# measures_schematic_12-22.net
KiCad netlist of a schematic drawn in EAGLE
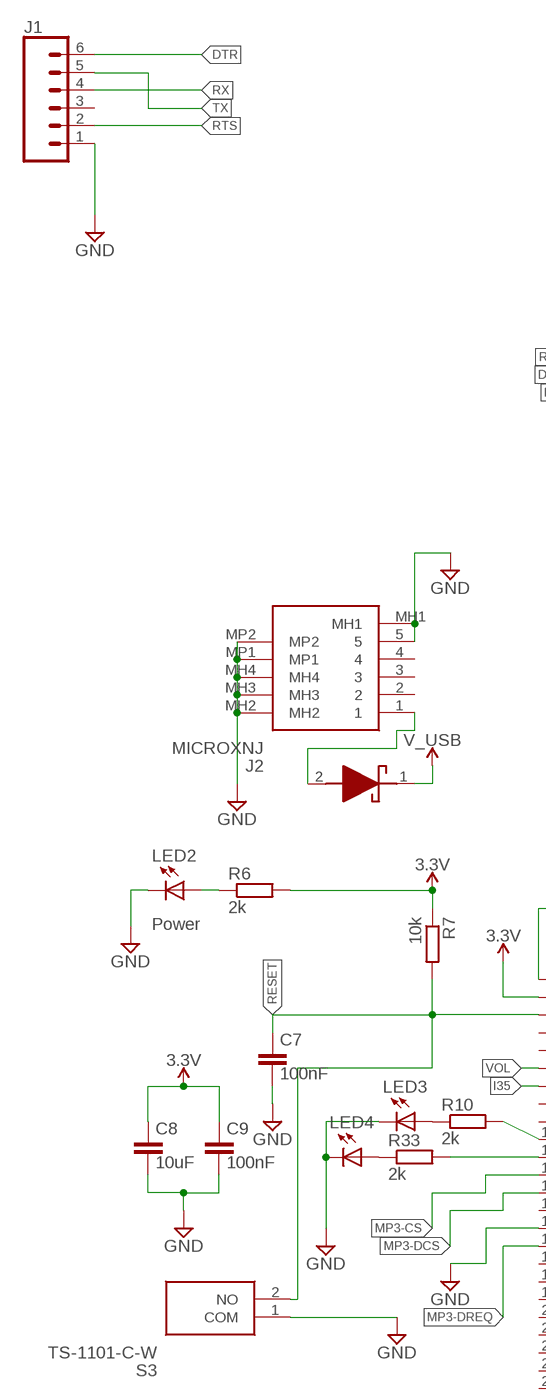
[diagram p0: schematic, sheet 1, part 1 of 2]
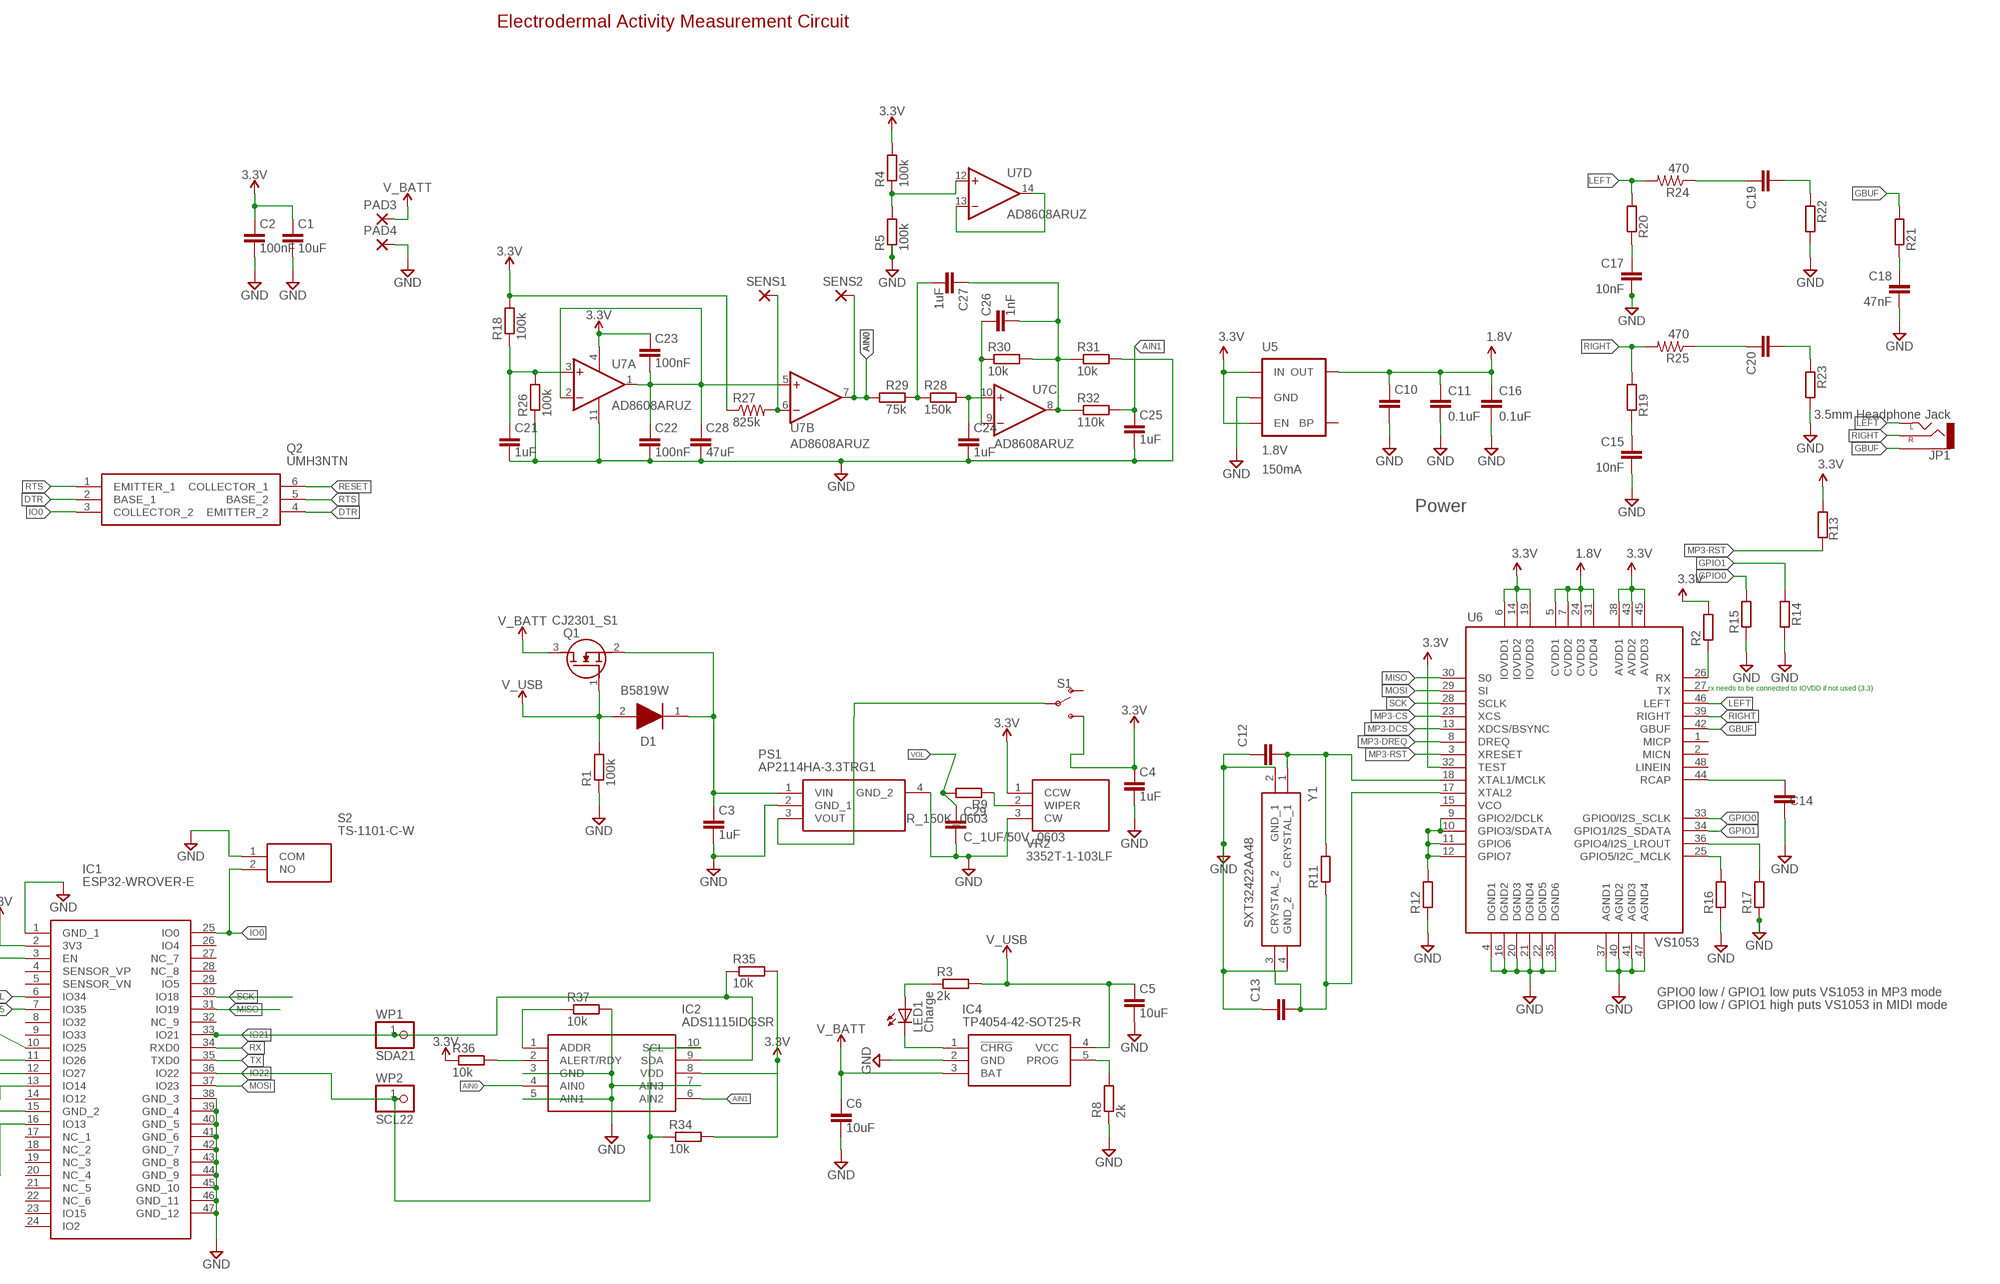
[diagram p1: schematic, sheet 1, part 2 of 2]

(export (version "E")
  (design (tool "Eeschema 10.0.6"))
  (components
    (comp (ref "C1")
      (value "10uF")
      (footprint "eagle-import:C0603")
      (fields (field (name "LCSC_PART") "C96446"))
      (libsource (lib "eagle-import") (part "C__060310UF/25V"))
    )
    (comp (ref "C2")
      (value "100nF")
      (footprint "eagle-import:C0603")
      (fields (field (name "LCSC_PART") "C14663"))
      (libsource (lib "eagle-import") (part "C__0603100NF/50V"))
    )
    (comp (ref "C3")
      (value "1uF")
      (footprint "eagle-import:C0402")
      (fields (field (name "LCSC_PART") "C52923"))
      (libsource (lib "eagle-import") (part "C__04021UF/25V"))
    )
    (comp (ref "C4")
      (value "1uF")
      (footprint "eagle-import:C0402")
      (fields (field (name "LCSC_PART") "C52923"))
      (libsource (lib "eagle-import") (part "C__04021UF/25V"))
    )
    (comp (ref "C5")
      (value "10uF")
      (footprint "eagle-import:C0603")
      (fields (field (name "LCSC_PART") "C96446"))
      (libsource (lib "eagle-import") (part "C__060310UF/25V"))
    )
    (comp (ref "C6")
      (value "10uF")
      (footprint "eagle-import:C0603")
      (fields (field (name "LCSC_PART") "C96446"))
      (libsource (lib "eagle-import") (part "C__060310UF/25V"))
    )
    (comp (ref "C7")
      (value "100nF")
      (footprint "eagle-import:C0603")
      (fields (field (name "LCSC_PART") "C14663"))
      (libsource (lib "eagle-import") (part "C__0603100NF/50V"))
    )
    (comp (ref "C8")
      (value "10uF")
      (footprint "eagle-import:C0603")
      (fields (field (name "LCSC_PART") "C96446"))
      (libsource (lib "eagle-import") (part "C__060310UF/25V"))
    )
    (comp (ref "C9")
      (value "100nF")
      (footprint "eagle-import:C0603")
      (fields (field (name "LCSC_PART") "C14663"))
      (libsource (lib "eagle-import") (part "C__0603100NF/50V"))
    )
    (comp (ref "C10")
      (value "10uF")
      (footprint "eagle-import:C0603")
      (fields (field (name "LCSC_PART") "C96446"))
      (libsource (lib "eagle-import") (part "C__060310UF/25V"))
    )
    (comp (ref "C11")
      (value "0.1uF")
      (footprint "eagle-import:0603-CAP")
      (libsource (lib "eagle-import") (part "0.1UF-25V(+80/-20%)(0603)"))
    )
    (comp (ref "C12")
      (value "22pF")
      (footprint "eagle-import:C0603")
      (fields (field (name "LCSC_PART") "C38523"))
      (libsource (lib "eagle-import") (part "C__060312PF/50V"))
    )
    (comp (ref "C13")
      (value "22pF")
      (footprint "eagle-import:C0603")
      (fields (field (name "LCSC_PART") "C38523"))
      (libsource (lib "eagle-import") (part "C__060312PF/50V"))
    )
    (comp (ref "C14")
      (value "1.0uF")
      (footprint "eagle-import:C0402")
      (fields (field (name "LCSC_PART") "C52923"))
      (libsource (lib "eagle-import") (part "C__04021UF/25V"))
    )
    (comp (ref "C15")
      (value "10nF")
      (footprint "eagle-import:0603-CAP")
      (libsource (lib "eagle-import") (part "10NF/10000PF-50V-10%(0603)"))
    )
    (comp (ref "C16")
      (value "0.1uF")
      (footprint "eagle-import:0603-CAP")
      (libsource (lib "eagle-import") (part "0.1UF-25V(+80/-20%)(0603)"))
    )
    (comp (ref "C17")
      (value "10nF")
      (footprint "eagle-import:0603-CAP")
      (libsource (lib "eagle-import") (part "10NF/10000PF-50V-10%(0603)"))
    )
    (comp (ref "C18")
      (value "47nF")
      (footprint "eagle-import:0603-CAP")
      (libsource (lib "eagle-import") (part "47NF(0.047UF/47000PF)-25V-5%(0603)SMD"))
    )
    (comp (ref "C19")
      (value "10uF")
      (footprint "eagle-import:C0603")
      (fields (field (name "LCSC_PART") "C96446"))
      (libsource (lib "eagle-import") (part "C__060310UF/25V"))
    )
    (comp (ref "C20")
      (value "10uF")
      (footprint "eagle-import:C0603")
      (fields (field (name "LCSC_PART") "C96446"))
      (libsource (lib "eagle-import") (part "C__060310UF/25V"))
    )
    (comp (ref "C21")
      (value "1uF")
      (footprint "eagle-import:C0402")
      (fields (field (name "LCSC_PART") "C52923"))
      (libsource (lib "eagle-import") (part "C__04021UF/25V"))
    )
    (comp (ref "C22")
      (value "100nF")
      (footprint "eagle-import:C0603")
      (fields (field (name "LCSC_PART") "C14663"))
      (libsource (lib "eagle-import") (part "C__0603100NF/50V"))
    )
    (comp (ref "C23")
      (value "100nF")
      (footprint "eagle-import:C0603")
      (fields (field (name "LCSC_PART") "C14663"))
      (libsource (lib "eagle-import") (part "C__0603100NF/50V"))
    )
    (comp (ref "C24")
      (value "1uF")
      (footprint "eagle-import:C0603")
      (fields (field (name "LCSC_PART") "C15849"))
      (libsource (lib "eagle-import") (part "C__06031UF/50V"))
    )
    (comp (ref "C25")
      (value "1uF")
      (footprint "eagle-import:C0402")
      (fields (field (name "LCSC_PART") "C52923"))
      (libsource (lib "eagle-import") (part "C__04021UF/25V"))
    )
    (comp (ref "C26")
      (value "1nF")
      (footprint "eagle-import:C0603")
      (fields (field (name "LCSC_PART") "C1588"))
      (libsource (lib "eagle-import") (part "C__06031NF/50V"))
    )
    (comp (ref "C27")
      (value "1uF")
      (footprint "eagle-import:C0603")
      (fields (field (name "LCSC_PART") "C15849"))
      (libsource (lib "eagle-import") (part "C__06031UF/50V"))
    )
    (comp (ref "C28")
      (value "47uF")
      (footprint "eagle-import:C1206")
      (fields (field (name "LCSC_PART") "C96123"))
      (libsource (lib "eagle-import") (part "C__120647UF/10V"))
    )
    (comp (ref "C29")
      (value "C_1UF/50V_0603")
      (footprint "eagle-import:C0603")
      (fields (field (name "LCSC_PART") "C15849"))
      (libsource (lib "eagle-import") (part "C__06031UF/50V"))
    )
    (comp (ref "D1")
      (value "B5819W")
      (footprint "eagle-import:SOD3716X125N")
      (libsource (lib "eagle-import") (part "B5819W"))
    )
    (comp (ref "D5")
      (value "BAT760-7")
      (footprint "eagle-import:SOD2513X120N")
      (fields (field (name "MOUSER_PART_NUMBER") "621-BAT760-7"))
      (libsource (lib "eagle-import") (part "BAT760-7"))
    )
    (comp (ref "IC1")
      (value "ESP32-WROVER-E")
      (footprint "eagle-import:ESP32WROVERE")
      (libsource (lib "eagle-import") (part "ESP32-WROVER-E"))
    )
    (comp (ref "IC2")
      (value "ADS1115IDGSR")
      (footprint "eagle-import:SOP50P490X110-10N")
      (fields (field (name "MOUSER_PART_NUMBER") "595-ADS1115IDGSR"))
      (libsource (lib "eagle-import") (part "ADS1115IDGSR"))
    )
    (comp (ref "IC4")
      (value "TP4054-42-SOT25-R")
      (footprint "eagle-import:SOT95P280X100-5N")
      (libsource (lib "eagle-import") (part "TP4054-42-SOT25-R"))
    )
    (comp (ref "J1")
      (value "CONN_06NO_SILK_FEMALE_PTH")
      (footprint "eagle-import:1X06_NO_SILK")
      (libsource (lib "eagle-import") (part "CONN_06NO_SILK_FEMALE_PTH"))
    )
    (comp (ref "J2")
      (value "MICROXNJ")
      (footprint "eagle-import:MICROXNJ")
      (libsource (lib "eagle-import") (part "MICROXNJ"))
    )
    (comp (ref "JP1")
      (value "3.5mm Headphone Jack")
      (footprint "eagle-import:AUDIO-JACK-3.5MM-SMD")
      (libsource (lib "eagle-import") (part "AUDIO-JACKSMD2"))
    )
    (comp (ref "LED1")
      (value "Charge")
      (footprint "eagle-import:CHIP-LED0603")
      (libsource (lib "eagle-import") (part "LEDCHIP-LED0603"))
    )
    (comp (ref "LED2")
      (value "Power")
      (footprint "eagle-import:CHIP-LED0603")
      (libsource (lib "eagle-import") (part "LEDCHIP-LED0603"))
    )
    (comp (ref "LED3")
      (value "Power")
      (footprint "eagle-import:CHIP-LED0603")
      (libsource (lib "eagle-import") (part "LEDCHIP-LED0603"))
    )
    (comp (ref "LED4")
      (value "Power")
      (footprint "eagle-import:CHIP-LED0603")
      (libsource (lib "eagle-import") (part "LEDCHIP-LED0603"))
    )
    (comp (ref "PAD3")
      (value "2,54/0,8")
      (footprint "eagle-import:2,54_0,8")
      (libsource (lib "eagle-import") (part "2,54/0,8"))
    )
    (comp (ref "PAD4")
      (value "2,54/0,8")
      (footprint "eagle-import:2,54_0,8")
      (libsource (lib "eagle-import") (part "2,54/0,8"))
    )
    (comp (ref "PS1")
      (value "AP2114HA-3.3TRG1")
      (footprint "eagle-import:SOT230P700X180-4N")
      (fields (field (name "MOUSER_PART_NUMBER") "621-AP2114HA-3.3TRG1"))
      (libsource (lib "eagle-import") (part "AP2114HA-3.3TRG1"))
    )
    (comp (ref "Q1")
      (value "CJ2301_S1")
      (footprint "eagle-import:SOT95P240X115-3N")
      (fields (field (name "MANUFACTURER_PART_NUMBER") "CJ2301 S1"))
      (libsource (lib "eagle-import") (part "CJ2301_S1"))
    )
    (comp (ref "Q2")
      (value "UMH3NTN")
      (footprint "eagle-import:UMH3NTN")
      (fields (field (name "MOUSER_PART_NUMBER") "755-UMH3NTN"))
      (libsource (lib "eagle-import") (part "UMH3NTN"))
    )
    (comp (ref "R1")
      (value "100k")
      (footprint "eagle-import:R0603")
      (fields (field (name "LCSC_PART") "C25803"))
      (libsource (lib "eagle-import") (part "R__0603100K"))
    )
    (comp (ref "R2")
      (value "100k")
      (footprint "eagle-import:R0603")
      (fields (field (name "LCSC_PART") "C25803"))
      (libsource (lib "eagle-import") (part "R__0603100K"))
    )
    (comp (ref "R3")
      (value "2k")
      (footprint "eagle-import:R0603")
      (fields (field (name "LCSC_PART") "C22975"))
      (libsource (lib "eagle-import") (part "R__06032K"))
    )
    (comp (ref "R4")
      (value "100k")
      (footprint "eagle-import:R0603")
      (fields (field (name "LCSC_PART") "C25803"))
      (libsource (lib "eagle-import") (part "R__0603100K"))
    )
    (comp (ref "R5")
      (value "100k")
      (footprint "eagle-import:R0603")
      (fields (field (name "LCSC_PART") "C25803"))
      (libsource (lib "eagle-import") (part "R__0603100K"))
    )
    (comp (ref "R6")
      (value "2k")
      (footprint "eagle-import:R0603")
      (fields (field (name "LCSC_PART") "C22975"))
      (libsource (lib "eagle-import") (part "R__06032K"))
    )
    (comp (ref "R7")
      (value "10k")
      (footprint "eagle-import:R0603")
      (fields (field (name "LCSC_PART") "C25804"))
      (libsource (lib "eagle-import") (part "R__060310K"))
    )
    (comp (ref "R8")
      (value "2k")
      (footprint "eagle-import:R0603")
      (fields (field (name "LCSC_PART") "C22975"))
      (libsource (lib "eagle-import") (part "R__06032K"))
    )
    (comp (ref "R9")
      (value "R_150K_0603")
      (footprint "eagle-import:R0603")
      (fields (field (name "LCSC_PART") "C22807"))
      (libsource (lib "eagle-import") (part "R__0603150K"))
    )
    (comp (ref "R10")
      (value "2k")
      (footprint "eagle-import:R0603")
      (fields (field (name "LCSC_PART") "C22975"))
      (libsource (lib "eagle-import") (part "R__06032K"))
    )
    (comp (ref "R11")
      (value "1M")
      (footprint "eagle-import:R0603")
      (fields (field (name "LCSC_PART") "C22935"))
      (libsource (lib "eagle-import") (part "R__06031M"))
    )
    (comp (ref "R12")
      (value "100k")
      (footprint "eagle-import:R0603")
      (fields (field (name "LCSC_PART") "C25803"))
      (libsource (lib "eagle-import") (part "R__0603100K"))
    )
    (comp (ref "R13")
      (value "100k")
      (footprint "eagle-import:R0603")
      (fields (field (name "LCSC_PART") "C25803"))
      (libsource (lib "eagle-import") (part "R__0603100K"))
    )
    (comp (ref "R14")
      (value "100k")
      (footprint "eagle-import:R0603")
      (fields (field (name "LCSC_PART") "C25803"))
      (libsource (lib "eagle-import") (part "R__0603100K"))
    )
    (comp (ref "R15")
      (value "100k")
      (footprint "eagle-import:R0603")
      (fields (field (name "LCSC_PART") "C25803"))
      (libsource (lib "eagle-import") (part "R__0603100K"))
    )
    (comp (ref "R16")
      (value "100k")
      (footprint "eagle-import:R0603")
      (fields (field (name "LCSC_PART") "C25803"))
      (libsource (lib "eagle-import") (part "R__0603100K"))
    )
    (comp (ref "R17")
      (value "100k")
      (footprint "eagle-import:R0603")
      (fields (field (name "LCSC_PART") "C25803"))
      (libsource (lib "eagle-import") (part "R__0603100K"))
    )
    (comp (ref "R18")
      (value "100k")
      (footprint "eagle-import:R0603")
      (fields (field (name "LCSC_PART") "C25803"))
      (libsource (lib "eagle-import") (part "R__0603100K"))
    )
    (comp (ref "R19")
      (value "20")
      (footprint "eagle-import:R0603")
      (fields (field (name "LCSC_PART") "C22950"))
      (libsource (lib "eagle-import") (part "R__060320R"))
    )
    (comp (ref "R20")
      (value "20")
      (footprint "eagle-import:R0603")
      (fields (field (name "LCSC_PART") "C22950"))
      (libsource (lib "eagle-import") (part "R__060320R"))
    )
    (comp (ref "R21")
      (value "10")
      (footprint "eagle-import:R0603")
      (fields (field (name "LCSC_PART") "C22859"))
      (libsource (lib "eagle-import") (part "R__060310R"))
    )
    (comp (ref "R22")
      (value "10K")
      (footprint "eagle-import:R0603")
      (fields (field (name "LCSC_PART") "C25804"))
      (libsource (lib "eagle-import") (part "R__060310K"))
    )
    (comp (ref "R23")
      (value "10K")
      (footprint "eagle-import:R0603")
      (fields (field (name "LCSC_PART") "C25804"))
      (libsource (lib "eagle-import") (part "R__060310K"))
    )
    (comp (ref "R24")
      (value "470")
      (footprint "eagle-import:0603-RES")
      (libsource (lib "eagle-import") (part "470OHM1/10W1%(0603)"))
    )
    (comp (ref "R25")
      (value "470")
      (footprint "eagle-import:0603-RES")
      (libsource (lib "eagle-import") (part "470OHM1/10W1%(0603)"))
    )
    (comp (ref "R26")
      (value "100k")
      (footprint "eagle-import:R0603")
      (fields (field (name "LCSC_PART") "C25803"))
      (libsource (lib "eagle-import") (part "R__0603100K"))
    )
    (comp (ref "R27")
      (value "825k")
      (footprint "eagle-import:R0402")
      (libsource (lib "eagle-import") (part "R-US_R0402"))
    )
    (comp (ref "R28")
      (value "150k")
      (footprint "eagle-import:R0402")
      (fields (field (name "LCSC_PART") "C25755"))
      (libsource (lib "eagle-import") (part "R__0402150K"))
    )
    (comp (ref "R29")
      (value "75k")
      (footprint "eagle-import:R0402")
      (fields (field (name "LCSC_PART") "C25798"))
      (libsource (lib "eagle-import") (part "R__040275K"))
    )
    (comp (ref "R30")
      (value "10k")
      (footprint "eagle-import:R0603")
      (fields (field (name "LCSC_PART") "C25804"))
      (libsource (lib "eagle-import") (part "R__060310K"))
    )
    (comp (ref "R31")
      (value "10k")
      (footprint "eagle-import:R0603")
      (fields (field (name "LCSC_PART") "C25804"))
      (libsource (lib "eagle-import") (part "R__060310K"))
    )
    (comp (ref "R32")
      (value "110k")
      (footprint "eagle-import:R0603")
      (fields (field (name "LCSC_PART") "C25805"))
      (libsource (lib "eagle-import") (part "R__0603110K"))
    )
    (comp (ref "R33")
      (value "2k")
      (footprint "eagle-import:R0603")
      (fields (field (name "LCSC_PART") "C22975"))
      (libsource (lib "eagle-import") (part "R__06032K"))
    )
    (comp (ref "R34")
      (value "10k")
      (footprint "eagle-import:R0603")
      (fields (field (name "LCSC_PART") "C25804"))
      (libsource (lib "eagle-import") (part "R__060310K"))
    )
    (comp (ref "R35")
      (value "10k")
      (footprint "eagle-import:R0603")
      (fields (field (name "LCSC_PART") "C25804"))
      (libsource (lib "eagle-import") (part "R__060310K"))
    )
    (comp (ref "R36")
      (value "10k")
      (footprint "eagle-import:R0603")
      (fields (field (name "LCSC_PART") "C25804"))
      (libsource (lib "eagle-import") (part "R__060310K"))
    )
    (comp (ref "R37")
      (value "10k")
      (footprint "eagle-import:R0603")
      (fields (field (name "LCSC_PART") "C25804"))
      (libsource (lib "eagle-import") (part "R__060310K"))
    )
    (comp (ref "S1")
      (value "SWITCH-SPDT-PTH-11.6X4.0MM")
      (footprint "eagle-import:SWITCH_SPDT_PTH_11.6X4.0MM")
      (libsource (lib "eagle-import") (part "SWITCH-SPDT-PTH-11.6X4.0MM"))
    )
    (comp (ref "S2")
      (value "TS-1101-C-W")
      (footprint "eagle-import:TS1101CW")
      (libsource (lib "eagle-import") (part "TS-1101-C-W"))
    )
    (comp (ref "S3")
      (value "TS-1101-C-W")
      (footprint "eagle-import:TS1101CW")
      (libsource (lib "eagle-import") (part "TS-1101-C-W"))
    )
    (comp (ref "SENS1")
      (value "2,54/0,8")
      (footprint "eagle-import:2,54_0,8")
      (libsource (lib "eagle-import") (part "2,54/0,8"))
    )
    (comp (ref "SENS2")
      (value "2,54/0,8")
      (footprint "eagle-import:2,54_0,8")
      (libsource (lib "eagle-import") (part "2,54/0,8"))
    )
    (comp (ref "U5")
      (value "1.8V")
      (footprint "eagle-import:SC70")
      (libsource (lib "eagle-import") (part "V_REG_SP62141.8V"))
    )
    (comp (ref "U6")
      (value "VS1053")
      (footprint "eagle-import:LQFP-48")
      (libsource (lib "eagle-import") (part "VS1033/1053SMD"))
    )
    (comp (ref "U7")
      (value "AD8608ARUZ")
      (footprint "eagle-import:TSSOP14")
      (fields (field (name "MF") "Analog Devices"))
      (libsource (lib "eagle-import") (part "AD8608ARUZ"))
    )
    (comp (ref "VR2")
      (value "3352T-1-103LF")
      (footprint "eagle-import:3352T1103LF")
      (fields (field (name "MOUSER_PART_NUMBER") "652-3352T-1-103LF"))
      (libsource (lib "eagle-import") (part "3352T-1-103LF"))
    )
    (comp (ref "WP1")
      (value "SDA21")
      (footprint "eagle-import:WPAD-1-0805")
      (libsource (lib "eagle-import") (part "WPAD-1-0805"))
    )
    (comp (ref "WP2")
      (value "SCL22")
      (footprint "eagle-import:WPAD-1-0805")
      (libsource (lib "eagle-import") (part "WPAD-1-0805"))
    )
    (comp (ref "Y1")
      (value "SXT32422AA48")
      (footprint "eagle-import:SXT32422AA48")
      (libsource (lib "eagle-import") (part "SXT32422AA48"))
    )
  )
  (nets
    (net (code "1") (name "1.8V") (class "Default")
      (node (ref "C10") (pin "1") (pinfunction "1_1") (pintype "passive"))
      (node (ref "C11") (pin "1") (pinfunction "1_1") (pintype "passive"))
      (node (ref "C16") (pin "1") (pinfunction "1_1") (pintype "passive"))
      (node (ref "U5") (pin "5") (pinfunction "OUT_5") (pintype "passive"))
      (node (ref "U6") (pin "24") (pinfunction "CVDD3_24") (pintype "bidirectional"))
      (node (ref "U6") (pin "31") (pinfunction "CVDD4_31") (pintype "bidirectional"))
      (node (ref "U6") (pin "5") (pinfunction "CVDD1_5") (pintype "bidirectional"))
      (node (ref "U6") (pin "7") (pinfunction "CVDD2_7") (pintype "bidirectional"))
    )
    (net (code "2") (name "3.3V") (class "Default")
      (node (ref "C1") (pin "1") (pinfunction "1_1") (pintype "passive"))
      (node (ref "C2") (pin "1") (pinfunction "1_1") (pintype "passive"))
      (node (ref "C23") (pin "1") (pinfunction "1_1") (pintype "passive"))
      (node (ref "C4") (pin "1") (pinfunction "1_1") (pintype "passive"))
      (node (ref "C8") (pin "1") (pinfunction "1_1") (pintype "passive"))
      (node (ref "C9") (pin "1") (pinfunction "1_1") (pintype "passive"))
      (node (ref "IC1") (pin "2") (pinfunction "3V3_2") (pintype "bidirectional"))
      (node (ref "IC2") (pin "8") (pinfunction "VDD_8") (pintype "bidirectional"))
      (node (ref "R13") (pin "2") (pinfunction "2_2") (pintype "passive"))
      (node (ref "R18") (pin "2") (pinfunction "2_2") (pintype "passive"))
      (node (ref "R2") (pin "2") (pinfunction "2_2") (pintype "passive"))
      (node (ref "R27") (pin "1") (pinfunction "1_1") (pintype "passive"))
      (node (ref "R34") (pin "2") (pinfunction "2_2") (pintype "passive"))
      (node (ref "R35") (pin "2") (pinfunction "2_2") (pintype "passive"))
      (node (ref "R36") (pin "1") (pinfunction "1_1") (pintype "passive"))
      (node (ref "R4") (pin "2") (pinfunction "2_2") (pintype "passive"))
      (node (ref "R6") (pin "2") (pinfunction "2_2") (pintype "passive"))
      (node (ref "R7") (pin "1") (pinfunction "1_1") (pintype "passive"))
      (node (ref "S1") (pin "3") (pinfunction "S_3") (pintype "passive"))
      (node (ref "U5") (pin "1") (pinfunction "IN_1") (pintype "input"))
      (node (ref "U5") (pin "3") (pinfunction "EN_3") (pintype "input"))
      (node (ref "U6") (pin "14") (pinfunction "IOVDD2_14") (pintype "bidirectional"))
      (node (ref "U6") (pin "19") (pinfunction "IOVDD3_19") (pintype "bidirectional"))
      (node (ref "U6") (pin "32") (pinfunction "TEST_32") (pintype "bidirectional"))
      (node (ref "U6") (pin "38") (pinfunction "AVDD1_38") (pintype "bidirectional"))
      (node (ref "U6") (pin "43") (pinfunction "AVDD2_43") (pintype "bidirectional"))
      (node (ref "U6") (pin "45") (pinfunction "AVDD3_45") (pintype "bidirectional"))
      (node (ref "U6") (pin "6") (pinfunction "IOVDD1_6") (pintype "bidirectional"))
      (node (ref "U7") (pin "4") (pinfunction "VCC_4") (pintype "power_in"))
      (node (ref "VR2") (pin "1") (pinfunction "CCW_1") (pintype "bidirectional"))
    )
    (net (code "3") (name "AIN0") (class "Default")
      (node (ref "IC2") (pin "4") (pinfunction "AIN0_4") (pintype "bidirectional"))
      (node (ref "R29") (pin "1") (pinfunction "1_1") (pintype "passive"))
      (node (ref "SENS2") (pin "1") (pinfunction "P_1") (pintype "passive"))
      (node (ref "U7") (pin "7") (pinfunction "OUT_7") (pintype "output"))
    )
    (net (code "4") (name "AIN1") (class "Default")
      (node (ref "C25") (pin "1") (pinfunction "1_1") (pintype "passive"))
      (node (ref "IC2") (pin "6") (pinfunction "AIN2_6") (pintype "bidirectional"))
      (node (ref "R32") (pin "2") (pinfunction "2_2") (pintype "passive"))
    )
    (net (code "5") (name "DTR") (class "Default")
      (node (ref "J1") (pin "6") (pinfunction "6_6") (pintype "passive"))
      (node (ref "Q2") (pin "2") (pinfunction "BASE_1_2") (pintype "bidirectional"))
      (node (ref "Q2") (pin "4") (pinfunction "EMITTER_2_4") (pintype "bidirectional"))
    )
    (net (code "6") (name "GBUF") (class "Default")
      (node (ref "JP1") (pin "SLEEVE") (pinfunction "SLEEVE_SLEEVE") (pintype "bidirectional"))
      (node (ref "R21") (pin "2") (pinfunction "2_2") (pintype "passive"))
      (node (ref "U6") (pin "42") (pinfunction "GBUF_42") (pintype "bidirectional"))
    )
    (net (code "7") (name "GND") (class "Default")
      (node (ref "C1") (pin "2") (pinfunction "2_2") (pintype "passive"))
      (node (ref "C10") (pin "2") (pinfunction "2_2") (pintype "passive"))
      (node (ref "C11") (pin "2") (pinfunction "2_2") (pintype "passive"))
      (node (ref "C12") (pin "1") (pinfunction "1_1") (pintype "passive"))
      (node (ref "C13") (pin "1") (pinfunction "1_1") (pintype "passive"))
      (node (ref "C14") (pin "1") (pinfunction "1_1") (pintype "passive"))
      (node (ref "C15") (pin "2") (pinfunction "2_2") (pintype "passive"))
      (node (ref "C16") (pin "2") (pinfunction "2_2") (pintype "passive"))
      (node (ref "C17") (pin "2") (pinfunction "2_2") (pintype "passive"))
      (node (ref "C18") (pin "2") (pinfunction "2_2") (pintype "passive"))
      (node (ref "C2") (pin "2") (pinfunction "2_2") (pintype "passive"))
      (node (ref "C21") (pin "2") (pinfunction "2_2") (pintype "passive"))
      (node (ref "C22") (pin "2") (pinfunction "2_2") (pintype "passive"))
      (node (ref "C24") (pin "2") (pinfunction "2_2") (pintype "passive"))
      (node (ref "C25") (pin "2") (pinfunction "2_2") (pintype "passive"))
      (node (ref "C28") (pin "2") (pinfunction "2_2") (pintype "passive"))
      (node (ref "C29") (pin "2") (pinfunction "2_2") (pintype "passive"))
      (node (ref "C3") (pin "2") (pinfunction "2_2") (pintype "passive"))
      (node (ref "C4") (pin "2") (pinfunction "2_2") (pintype "passive"))
      (node (ref "C5") (pin "2") (pinfunction "2_2") (pintype "passive"))
      (node (ref "C6") (pin "2") (pinfunction "2_2") (pintype "passive"))
      (node (ref "C7") (pin "2") (pinfunction "2_2") (pintype "passive"))
      (node (ref "C8") (pin "2") (pinfunction "2_2") (pintype "passive"))
      (node (ref "C9") (pin "2") (pinfunction "2_2") (pintype "passive"))
      (node (ref "IC1") (pin "1") (pinfunction "GND_1_1") (pintype "bidirectional"))
      (node (ref "IC1") (pin "15") (pinfunction "GND_2_15") (pintype "bidirectional"))
      (node (ref "IC1") (pin "38") (pinfunction "GND_3_38") (pintype "bidirectional"))
      (node (ref "IC1") (pin "39") (pinfunction "GND_4_39") (pintype "bidirectional"))
      (node (ref "IC1") (pin "40") (pinfunction "GND_5_40") (pintype "bidirectional"))
      (node (ref "IC1") (pin "41") (pinfunction "GND_6_41") (pintype "bidirectional"))
      (node (ref "IC1") (pin "42") (pinfunction "GND_7_42") (pintype "bidirectional"))
      (node (ref "IC1") (pin "43") (pinfunction "GND_8_43") (pintype "bidirectional"))
      (node (ref "IC1") (pin "44") (pinfunction "GND_9_44") (pintype "bidirectional"))
      (node (ref "IC1") (pin "45") (pinfunction "GND_10_45") (pintype "bidirectional"))
      (node (ref "IC1") (pin "46") (pinfunction "GND_11_46") (pintype "bidirectional"))
      (node (ref "IC1") (pin "47") (pinfunction "GND_12_47") (pintype "bidirectional"))
      (node (ref "IC2") (pin "3") (pinfunction "GND_3") (pintype "bidirectional"))
      (node (ref "IC2") (pin "5") (pinfunction "AIN1_5") (pintype "bidirectional"))
      (node (ref "IC2") (pin "7") (pinfunction "AIN3_7") (pintype "bidirectional"))
      (node (ref "IC4") (pin "2") (pinfunction "GND_2") (pintype "bidirectional"))
      (node (ref "J1") (pin "1") (pinfunction "1_1") (pintype "passive"))
      (node (ref "J2") (pin "5") (pinfunction "5_5") (pintype "bidirectional"))
      (node (ref "J2") (pin "MH1") (pinfunction "MH1_MH1") (pintype "bidirectional"))
      (node (ref "J2") (pin "MH2") (pinfunction "MH2_MH2") (pintype "bidirectional"))
      (node (ref "J2") (pin "MH3") (pinfunction "MH3_MH3") (pintype "bidirectional"))
      (node (ref "J2") (pin "MH4") (pinfunction "MH4_MH4") (pintype "bidirectional"))
      (node (ref "J2") (pin "MP1") (pinfunction "MP1_MP1") (pintype "bidirectional"))
      (node (ref "J2") (pin "MP2") (pinfunction "MP2_MP2") (pintype "bidirectional"))
      (node (ref "LED2") (pin "C") (pinfunction "C_C") (pintype "passive"))
      (node (ref "LED3") (pin "C") (pinfunction "C_C") (pintype "passive"))
      (node (ref "LED4") (pin "C") (pinfunction "C_C") (pintype "passive"))
      (node (ref "PAD4") (pin "1") (pinfunction "P_1") (pintype "passive"))
      (node (ref "PS1") (pin "2") (pinfunction "GND_1_2") (pintype "power_in"))
      (node (ref "PS1") (pin "4") (pinfunction "GND_2_4") (pintype "power_in"))
      (node (ref "R1") (pin "1") (pinfunction "1_1") (pintype "passive"))
      (node (ref "R12") (pin "1") (pinfunction "1_1") (pintype "passive"))
      (node (ref "R14") (pin "1") (pinfunction "1_1") (pintype "passive"))
      (node (ref "R15") (pin "1") (pinfunction "1_1") (pintype "passive"))
      (node (ref "R16") (pin "1") (pinfunction "1_1") (pintype "passive"))
      (node (ref "R17") (pin "1") (pinfunction "1_1") (pintype "passive"))
      (node (ref "R22") (pin "2") (pinfunction "2_2") (pintype "passive"))
      (node (ref "R23") (pin "2") (pinfunction "2_2") (pintype "passive"))
      (node (ref "R26") (pin "1") (pinfunction "1_1") (pintype "passive"))
      (node (ref "R31") (pin "2") (pinfunction "2_2") (pintype "passive"))
      (node (ref "R37") (pin "2") (pinfunction "2_2") (pintype "passive"))
      (node (ref "R5") (pin "1") (pinfunction "1_1") (pintype "passive"))
      (node (ref "R8") (pin "1") (pinfunction "1_1") (pintype "passive"))
      (node (ref "S2") (pin "1") (pinfunction "COM_1") (pintype "bidirectional"))
      (node (ref "S3") (pin "1") (pinfunction "COM_1") (pintype "bidirectional"))
      (node (ref "U5") (pin "2") (pinfunction "GND_2") (pintype "input"))
      (node (ref "U6") (pin "16") (pinfunction "DGND2_16") (pintype "bidirectional"))
      (node (ref "U6") (pin "20") (pinfunction "DGND3_20") (pintype "bidirectional"))
      (node (ref "U6") (pin "21") (pinfunction "DGND4_21") (pintype "bidirectional"))
      (node (ref "U6") (pin "22") (pinfunction "DGND5_22") (pintype "bidirectional"))
      (node (ref "U6") (pin "35") (pinfunction "DGND6_35") (pintype "bidirectional"))
      (node (ref "U6") (pin "37") (pinfunction "AGND1_37") (pintype "bidirectional"))
      (node (ref "U6") (pin "4") (pinfunction "DGND1_4") (pintype "bidirectional"))
      (node (ref "U6") (pin "40") (pinfunction "AGND2_40") (pintype "bidirectional"))
      (node (ref "U6") (pin "41") (pinfunction "AGND3_41") (pintype "bidirectional"))
      (node (ref "U6") (pin "47") (pinfunction "AGND4_47") (pintype "bidirectional"))
      (node (ref "U7") (pin "11") (pinfunction "GND_11") (pintype "power_in"))
      (node (ref "VR2") (pin "3") (pinfunction "CW_3") (pintype "bidirectional"))
      (node (ref "Y1") (pin "2") (pinfunction "GND_1_2") (pintype "bidirectional"))
      (node (ref "Y1") (pin "4") (pinfunction "GND_2_4") (pintype "bidirectional"))
    )
    (net (code "8") (name "GPIO0") (class "Default")
      (node (ref "R15") (pin "2") (pinfunction "2_2") (pintype "passive"))
      (node (ref "U6") (pin "33") (pinfunction "GPIO0/I2S_SCLK_33") (pintype "bidirectional"))
    )
    (net (code "9") (name "GPIO1") (class "Default")
      (node (ref "R14") (pin "2") (pinfunction "2_2") (pintype "passive"))
      (node (ref "U6") (pin "34") (pinfunction "GPIO1/I2S_SDATA_34") (pintype "bidirectional"))
    )
    (net (code "10") (name "I35") (class "Default")
      (node (ref "IC1") (pin "7") (pinfunction "IO35_7") (pintype "bidirectional"))
    )
    (net (code "11") (name "IO0") (class "Default")
      (node (ref "IC1") (pin "25") (pinfunction "IO0_25") (pintype "bidirectional"))
      (node (ref "Q2") (pin "3") (pinfunction "COLLECTOR_2_3") (pintype "bidirectional"))
      (node (ref "S2") (pin "2") (pinfunction "NO_2") (pintype "bidirectional"))
    )
    (net (code "12") (name "IO21") (class "Default")
      (node (ref "IC1") (pin "33") (pinfunction "IO21_33") (pintype "bidirectional"))
      (node (ref "IC2") (pin "9") (pinfunction "SDA_9") (pintype "bidirectional"))
      (node (ref "R35") (pin "1") (pinfunction "1_1") (pintype "passive"))
      (node (ref "WP1") (pin "1") (pinfunction "1_1") (pintype "passive"))
    )
    (net (code "13") (name "IO22") (class "Default")
      (node (ref "IC1") (pin "36") (pinfunction "IO22_36") (pintype "bidirectional"))
      (node (ref "IC2") (pin "10") (pinfunction "SCL_10") (pintype "bidirectional"))
      (node (ref "R34") (pin "1") (pinfunction "1_1") (pintype "passive"))
      (node (ref "WP2") (pin "1") (pinfunction "1_1") (pintype "passive"))
    )
    (net (code "14") (name "LEFT") (class "Default")
      (node (ref "JP1") (pin "TIP") (pinfunction "LEFT_TIP") (pintype "bidirectional"))
      (node (ref "R20") (pin "2") (pinfunction "2_2") (pintype "passive"))
      (node (ref "R24") (pin "2") (pinfunction "2_2") (pintype "passive"))
      (node (ref "U6") (pin "46") (pinfunction "LEFT_46") (pintype "bidirectional"))
    )
    (net (code "15") (name "MISO") (class "Default")
      (node (ref "IC1") (pin "31") (pinfunction "IO19_31") (pintype "bidirectional"))
      (node (ref "U6") (pin "30") (pinfunction "S0_30") (pintype "bidirectional"))
    )
    (net (code "16") (name "MOSI") (class "Default")
      (node (ref "IC1") (pin "37") (pinfunction "IO23_37") (pintype "bidirectional"))
      (node (ref "U6") (pin "29") (pinfunction "SI_29") (pintype "bidirectional"))
    )
    (net (code "17") (name "MP3-CS") (class "Default")
      (node (ref "IC1") (pin "12") (pinfunction "IO27_12") (pintype "bidirectional"))
      (node (ref "U6") (pin "23") (pinfunction "XCS_23") (pintype "bidirectional"))
    )
    (net (code "18") (name "MP3-DCS") (class "Default")
      (node (ref "IC1") (pin "13") (pinfunction "IO14_13") (pintype "bidirectional"))
      (node (ref "U6") (pin "13") (pinfunction "XDCS/BSYNC_13") (pintype "bidirectional"))
    )
    (net (code "19") (name "MP3-DREQ") (class "Default")
      (node (ref "IC1") (pin "16") (pinfunction "IO13_16") (pintype "bidirectional"))
      (node (ref "U6") (pin "8") (pinfunction "DREQ_8") (pintype "bidirectional"))
    )
    (net (code "20") (name "MP3-RST") (class "Default")
      (node (ref "R13") (pin "1") (pinfunction "1_1") (pintype "passive"))
      (node (ref "U6") (pin "3") (pinfunction "XRESET_3") (pintype "bidirectional"))
    )
    (net (code "21") (name "Net-(C15-Pad1)") (class "Default")
      (node (ref "C15") (pin "1") (pinfunction "1_1") (pintype "passive"))
      (node (ref "R19") (pin "1") (pinfunction "1_1") (pintype "passive"))
    )
    (net (code "22") (name "Net-(C17-Pad1)") (class "Default")
      (node (ref "C17") (pin "1") (pinfunction "1_1") (pintype "passive"))
      (node (ref "R20") (pin "1") (pinfunction "1_1") (pintype "passive"))
    )
    (net (code "23") (name "Net-(C18-Pad1)") (class "Default")
      (node (ref "C18") (pin "1") (pinfunction "1_1") (pintype "passive"))
      (node (ref "R21") (pin "1") (pinfunction "1_1") (pintype "passive"))
    )
    (net (code "24") (name "Net-(C19-Pad1)") (class "Default")
      (node (ref "C19") (pin "1") (pinfunction "1_1") (pintype "passive"))
      (node (ref "R24") (pin "1") (pinfunction "1_1") (pintype "passive"))
    )
    (net (code "25") (name "Net-(C19-Pad2)") (class "Default")
      (node (ref "C19") (pin "2") (pinfunction "2_2") (pintype "passive"))
      (node (ref "R22") (pin "1") (pinfunction "1_1") (pintype "passive"))
    )
    (net (code "26") (name "Net-(C20-Pad1)") (class "Default")
      (node (ref "C20") (pin "1") (pinfunction "1_1") (pintype "passive"))
      (node (ref "R25") (pin "1") (pinfunction "1_1") (pintype "passive"))
    )
    (net (code "27") (name "Net-(C20-Pad2)") (class "Default")
      (node (ref "C20") (pin "2") (pinfunction "2_2") (pintype "passive"))
      (node (ref "R23") (pin "1") (pinfunction "1_1") (pintype "passive"))
    )
    (net (code "28") (name "Net-(C27-Pad2)") (class "Default")
      (node (ref "C27") (pin "2") (pinfunction "2_2") (pintype "passive"))
      (node (ref "R28") (pin "1") (pinfunction "1_1") (pintype "passive"))
      (node (ref "R29") (pin "2") (pinfunction "2_2") (pintype "passive"))
    )
    (net (code "29") (name "Net-(D1-K)") (class "Default")
      (node (ref "C3") (pin "1") (pinfunction "1_1") (pintype "passive"))
      (node (ref "D1") (pin "1") (pinfunction "K_1") (pintype "bidirectional"))
      (node (ref "PS1") (pin "1") (pinfunction "VIN_1") (pintype "input"))
      (node (ref "Q1") (pin "2") (pinfunction "S_2") (pintype "bidirectional"))
    )
    (net (code "30") (name "Net-(D5-A)") (class "Default")
      (node (ref "D5") (pin "2") (pinfunction "A_2") (pintype "bidirectional"))
      (node (ref "J2") (pin "1") (pinfunction "1_1") (pintype "bidirectional"))
    )
    (net (code "31") (name "Net-(IC1-IO25)") (class "Default")
      (node (ref "IC1") (pin "10") (pinfunction "IO25_10") (pintype "bidirectional"))
      (node (ref "R10") (pin "2") (pinfunction "2_2") (pintype "passive"))
    )
    (net (code "32") (name "Net-(IC1-IO26)") (class "Default")
      (node (ref "IC1") (pin "11") (pinfunction "IO26_11") (pintype "bidirectional"))
      (node (ref "R33") (pin "2") (pinfunction "2_2") (pintype "passive"))
    )
    (net (code "33") (name "Net-(IC2-ADDR)") (class "Default")
      (node (ref "IC2") (pin "1") (pinfunction "ADDR_1") (pintype "bidirectional"))
      (node (ref "R37") (pin "1") (pinfunction "1_1") (pintype "passive"))
    )
    (net (code "34") (name "Net-(IC2-ALERT{slash}RDY)") (class "Default")
      (node (ref "IC2") (pin "2") (pinfunction "ALERT/RDY_2") (pintype "bidirectional"))
      (node (ref "R36") (pin "2") (pinfunction "2_2") (pintype "passive"))
    )
    (net (code "35") (name "Net-(IC4-PROG)") (class "Default")
      (node (ref "IC4") (pin "5") (pinfunction "PROG_5") (pintype "bidirectional"))
      (node (ref "R8") (pin "2") (pinfunction "2_2") (pintype "passive"))
    )
    (net (code "36") (name "Net-(IC4-~{CHRG})") (class "Default")
      (node (ref "IC4") (pin "1") (pinfunction "~{CHRG}_1") (pintype "bidirectional"))
      (node (ref "LED1") (pin "C") (pinfunction "C_C") (pintype "passive"))
    )
    (net (code "37") (name "Net-(LED1-PadA)") (class "Default")
      (node (ref "LED1") (pin "A") (pinfunction "A_A") (pintype "passive"))
      (node (ref "R3") (pin "1") (pinfunction "1_1") (pintype "passive"))
    )
    (net (code "38") (name "Net-(LED2-PadA)") (class "Default")
      (node (ref "LED2") (pin "A") (pinfunction "A_A") (pintype "passive"))
      (node (ref "R6") (pin "1") (pinfunction "1_1") (pintype "passive"))
    )
    (net (code "39") (name "Net-(LED3-PadA)") (class "Default")
      (node (ref "LED3") (pin "A") (pinfunction "A_A") (pintype "passive"))
      (node (ref "R10") (pin "1") (pinfunction "1_1") (pintype "passive"))
    )
    (net (code "40") (name "Net-(LED4-PadA)") (class "Default")
      (node (ref "LED4") (pin "A") (pinfunction "A_A") (pintype "passive"))
      (node (ref "R33") (pin "1") (pinfunction "1_1") (pintype "passive"))
    )
    (net (code "41") (name "Net-(PS1-VOUT)") (class "Default")
      (node (ref "PS1") (pin "3") (pinfunction "VOUT_3") (pintype "output"))
      (node (ref "S1") (pin "2") (pinfunction "P_2") (pintype "passive"))
    )
    (net (code "42") (name "Net-(SENS1-P)") (class "Default")
      (node (ref "R27") (pin "2") (pinfunction "2_2") (pintype "passive"))
      (node (ref "SENS1") (pin "1") (pinfunction "P_1") (pintype "passive"))
      (node (ref "U7") (pin "6") (pinfunction "-IN_6") (pintype "input"))
    )
    (net (code "43") (name "Net-(U6-GPIO2{slash}DCLK)") (class "Default")
      (node (ref "R12") (pin "2") (pinfunction "2_2") (pintype "passive"))
      (node (ref "U6") (pin "10") (pinfunction "GPIO3/SDATA_10") (pintype "bidirectional"))
      (node (ref "U6") (pin "11") (pinfunction "GPIO6_11") (pintype "bidirectional"))
      (node (ref "U6") (pin "12") (pinfunction "GPIO7_12") (pintype "bidirectional"))
      (node (ref "U6") (pin "9") (pinfunction "GPIO2/DCLK_9") (pintype "bidirectional"))
    )
    (net (code "44") (name "Net-(U6-GPIO4{slash}I2S_LROUT)") (class "Default")
      (node (ref "R17") (pin "2") (pinfunction "2_2") (pintype "passive"))
      (node (ref "U6") (pin "36") (pinfunction "GPIO4/I2S_LROUT_36") (pintype "bidirectional"))
    )
    (net (code "45") (name "Net-(U6-GPIO5{slash}I2C_MCLK)") (class "Default")
      (node (ref "R16") (pin "2") (pinfunction "2_2") (pintype "passive"))
      (node (ref "U6") (pin "25") (pinfunction "GPIO5/I2C_MCLK_25") (pintype "bidirectional"))
    )
    (net (code "46") (name "Net-(U6-RCAP)") (class "Default")
      (node (ref "C14") (pin "2") (pinfunction "2_2") (pintype "passive"))
      (node (ref "U6") (pin "44") (pinfunction "RCAP_44") (pintype "bidirectional"))
    )
    (net (code "47") (name "Net-(U6-RX)") (class "Default")
      (node (ref "R2") (pin "1") (pinfunction "1_1") (pintype "passive"))
      (node (ref "U6") (pin "26") (pinfunction "RX_26") (pintype "bidirectional"))
    )
    (net (code "48") (name "Net-(U6-XTAL1{slash}MCLK)") (class "Default")
      (node (ref "C12") (pin "2") (pinfunction "2_2") (pintype "passive"))
      (node (ref "R11") (pin "2") (pinfunction "2_2") (pintype "passive"))
      (node (ref "U6") (pin "18") (pinfunction "XTAL1/MCLK_18") (pintype "bidirectional"))
      (node (ref "Y1") (pin "1") (pinfunction "CRYSTAL_1_1") (pintype "bidirectional"))
    )
    (net (code "49") (name "Net-(U6-XTAL2)") (class "Default")
      (node (ref "C13") (pin "2") (pinfunction "2_2") (pintype "passive"))
      (node (ref "R11") (pin "1") (pinfunction "1_1") (pintype "passive"))
      (node (ref "U6") (pin "17") (pinfunction "XTAL2_17") (pintype "bidirectional"))
      (node (ref "Y1") (pin "3") (pinfunction "CRYSTAL_2_3") (pintype "bidirectional"))
    )
    (net (code "50") (name "Net-(U7A-+IN)") (class "Default")
      (node (ref "C21") (pin "1") (pinfunction "1_1") (pintype "passive"))
      (node (ref "R18") (pin "1") (pinfunction "1_1") (pintype "passive"))
      (node (ref "R26") (pin "2") (pinfunction "2_2") (pintype "passive"))
      (node (ref "U7") (pin "3") (pinfunction "+IN_3") (pintype "input"))
    )
    (net (code "51") (name "Net-(U7A--IN)") (class "Default")
      (node (ref "C22") (pin "1") (pinfunction "1_1") (pintype "passive"))
      (node (ref "C23") (pin "2") (pinfunction "2_2") (pintype "passive"))
      (node (ref "C28") (pin "1") (pinfunction "1_1") (pintype "passive"))
      (node (ref "U7") (pin "1") (pinfunction "OUT_1") (pintype "output"))
      (node (ref "U7") (pin "2") (pinfunction "-IN_2") (pintype "input"))
      (node (ref "U7") (pin "5") (pinfunction "+IN_5") (pintype "input"))
    )
    (net (code "52") (name "Net-(U7C-+IN)") (class "Default")
      (node (ref "C24") (pin "1") (pinfunction "1_1") (pintype "passive"))
      (node (ref "R28") (pin "2") (pinfunction "2_2") (pintype "passive"))
      (node (ref "U7") (pin "10") (pinfunction "+IN_10") (pintype "input"))
    )
    (net (code "53") (name "Net-(U7C--IN)") (class "Default")
      (node (ref "C26") (pin "1") (pinfunction "1_1") (pintype "passive"))
      (node (ref "R30") (pin "1") (pinfunction "1_1") (pintype "passive"))
      (node (ref "U7") (pin "9") (pinfunction "-IN_9") (pintype "input"))
    )
    (net (code "54") (name "Net-(U7C-OUT)") (class "Default")
      (node (ref "C26") (pin "2") (pinfunction "2_2") (pintype "passive"))
      (node (ref "C27") (pin "1") (pinfunction "1_1") (pintype "passive"))
      (node (ref "R30") (pin "2") (pinfunction "2_2") (pintype "passive"))
      (node (ref "R31") (pin "1") (pinfunction "1_1") (pintype "passive"))
      (node (ref "R32") (pin "1") (pinfunction "1_1") (pintype "passive"))
      (node (ref "U7") (pin "8") (pinfunction "OUT_8") (pintype "output"))
    )
    (net (code "55") (name "Net-(U7D-+IN)") (class "Default")
      (node (ref "R4") (pin "1") (pinfunction "1_1") (pintype "passive"))
      (node (ref "R5") (pin "2") (pinfunction "2_2") (pintype "passive"))
      (node (ref "U7") (pin "12") (pinfunction "+IN_12") (pintype "input"))
    )
    (net (code "56") (name "Net-(U7D--IN)") (class "Default")
      (node (ref "U7") (pin "13") (pinfunction "-IN_13") (pintype "input"))
      (node (ref "U7") (pin "14") (pinfunction "OUT_14") (pintype "output"))
    )
    (net (code "57") (name "Net-(VR2-WIPER)") (class "Default")
      (node (ref "R9") (pin "1") (pinfunction "1_1") (pintype "passive"))
      (node (ref "VR2") (pin "2") (pinfunction "WIPER_2") (pintype "bidirectional"))
    )
    (net (code "58") (name "RESET") (class "Default")
      (node (ref "C7") (pin "1") (pinfunction "1_1") (pintype "passive"))
      (node (ref "IC1") (pin "3") (pinfunction "EN_3") (pintype "bidirectional"))
      (node (ref "Q2") (pin "6") (pinfunction "COLLECTOR_1_6") (pintype "bidirectional"))
      (node (ref "R7") (pin "2") (pinfunction "2_2") (pintype "passive"))
      (node (ref "S3") (pin "2") (pinfunction "NO_2") (pintype "bidirectional"))
    )
    (net (code "59") (name "RIGHT") (class "Default")
      (node (ref "JP1") (pin "RING") (pinfunction "RIGHT_RING") (pintype "bidirectional"))
      (node (ref "R19") (pin "2") (pinfunction "2_2") (pintype "passive"))
      (node (ref "R25") (pin "2") (pinfunction "2_2") (pintype "passive"))
      (node (ref "U6") (pin "39") (pinfunction "RIGHT_39") (pintype "bidirectional"))
    )
    (net (code "60") (name "RTS") (class "Default")
      (node (ref "J1") (pin "2") (pinfunction "2_2") (pintype "passive"))
      (node (ref "Q2") (pin "1") (pinfunction "EMITTER_1_1") (pintype "bidirectional"))
      (node (ref "Q2") (pin "5") (pinfunction "BASE_2_5") (pintype "bidirectional"))
    )
    (net (code "61") (name "RX") (class "Default")
      (node (ref "IC1") (pin "34") (pinfunction "RXD0_34") (pintype "bidirectional"))
      (node (ref "J1") (pin "4") (pinfunction "4_4") (pintype "passive"))
    )
    (net (code "62") (name "SCK") (class "Default")
      (node (ref "IC1") (pin "30") (pinfunction "IO18_30") (pintype "bidirectional"))
      (node (ref "U6") (pin "28") (pinfunction "SCLK_28") (pintype "bidirectional"))
    )
    (net (code "63") (name "TX") (class "Default")
      (node (ref "IC1") (pin "35") (pinfunction "TXD0_35") (pintype "bidirectional"))
      (node (ref "J1") (pin "5") (pinfunction "5_5") (pintype "passive"))
    )
    (net (code "64") (name "VOL") (class "Default")
      (node (ref "C29") (pin "1") (pinfunction "1_1") (pintype "passive"))
      (node (ref "IC1") (pin "6") (pinfunction "IO34_6") (pintype "bidirectional"))
      (node (ref "R9") (pin "2") (pinfunction "2_2") (pintype "passive"))
    )
    (net (code "65") (name "V_BATT") (class "Default")
      (node (ref "C6") (pin "1") (pinfunction "1_1") (pintype "passive"))
      (node (ref "IC4") (pin "3") (pinfunction "BAT_3") (pintype "bidirectional"))
      (node (ref "PAD3") (pin "1") (pinfunction "P_1") (pintype "passive"))
      (node (ref "Q1") (pin "3") (pinfunction "D_3") (pintype "bidirectional"))
    )
    (net (code "66") (name "V_USB") (class "Default")
      (node (ref "C5") (pin "1") (pinfunction "1_1") (pintype "passive"))
      (node (ref "D1") (pin "2") (pinfunction "A_2") (pintype "bidirectional"))
      (node (ref "D5") (pin "1") (pinfunction "K_1") (pintype "bidirectional"))
      (node (ref "IC4") (pin "4") (pinfunction "VCC_4") (pintype "bidirectional"))
      (node (ref "Q1") (pin "1") (pinfunction "G_1") (pintype "bidirectional"))
      (node (ref "R1") (pin "2") (pinfunction "2_2") (pintype "passive"))
      (node (ref "R3") (pin "2") (pinfunction "2_2") (pintype "passive"))
    )
    (net (code "67") (name "unconnected-(IC1-IO2-Pad24)") (class "Default")
      (node (ref "IC1") (pin "24") (pinfunction "IO2_24") (pintype "bidirectional"))
    )
    (net (code "68") (name "unconnected-(IC1-IO4-Pad26)") (class "Default")
      (node (ref "IC1") (pin "26") (pinfunction "IO4_26") (pintype "bidirectional"))
    )
    (net (code "69") (name "unconnected-(IC1-IO5-Pad29)") (class "Default")
      (node (ref "IC1") (pin "29") (pinfunction "IO5_29") (pintype "bidirectional"))
    )
    (net (code "70") (name "unconnected-(IC1-IO12-Pad14)") (class "Default")
      (node (ref "IC1") (pin "14") (pinfunction "IO12_14") (pintype "bidirectional"))
    )
    (net (code "71") (name "unconnected-(IC1-IO15-Pad23)") (class "Default")
      (node (ref "IC1") (pin "23") (pinfunction "IO15_23") (pintype "bidirectional"))
    )
    (net (code "72") (name "unconnected-(IC1-IO32-Pad8)") (class "Default")
      (node (ref "IC1") (pin "8") (pinfunction "IO32_8") (pintype "bidirectional"))
    )
    (net (code "73") (name "unconnected-(IC1-IO33-Pad9)") (class "Default")
      (node (ref "IC1") (pin "9") (pinfunction "IO33_9") (pintype "bidirectional"))
    )
    (net (code "74") (name "unconnected-(IC1-NC_1-Pad17)") (class "Default")
      (node (ref "IC1") (pin "17") (pinfunction "NC_1_17") (pintype "bidirectional"))
    )
    (net (code "75") (name "unconnected-(IC1-NC_2-Pad18)") (class "Default")
      (node (ref "IC1") (pin "18") (pinfunction "NC_2_18") (pintype "bidirectional"))
    )
    (net (code "76") (name "unconnected-(IC1-NC_3-Pad19)") (class "Default")
      (node (ref "IC1") (pin "19") (pinfunction "NC_3_19") (pintype "bidirectional"))
    )
    (net (code "77") (name "unconnected-(IC1-NC_4-Pad20)") (class "Default")
      (node (ref "IC1") (pin "20") (pinfunction "NC_4_20") (pintype "bidirectional"))
    )
    (net (code "78") (name "unconnected-(IC1-NC_5-Pad21)") (class "Default")
      (node (ref "IC1") (pin "21") (pinfunction "NC_5_21") (pintype "bidirectional"))
    )
    (net (code "79") (name "unconnected-(IC1-NC_6-Pad22)") (class "Default")
      (node (ref "IC1") (pin "22") (pinfunction "NC_6_22") (pintype "bidirectional"))
    )
    (net (code "80") (name "unconnected-(IC1-NC_7-Pad27)") (class "Default")
      (node (ref "IC1") (pin "27") (pinfunction "NC_7_27") (pintype "bidirectional"))
    )
    (net (code "81") (name "unconnected-(IC1-NC_8-Pad28)") (class "Default")
      (node (ref "IC1") (pin "28") (pinfunction "NC_8_28") (pintype "bidirectional"))
    )
    (net (code "82") (name "unconnected-(IC1-NC_9-Pad32)") (class "Default")
      (node (ref "IC1") (pin "32") (pinfunction "NC_9_32") (pintype "bidirectional"))
    )
    (net (code "83") (name "unconnected-(IC1-SENSOR_VN-Pad5)") (class "Default")
      (node (ref "IC1") (pin "5") (pinfunction "SENSOR_VN_5") (pintype "bidirectional"))
    )
    (net (code "84") (name "unconnected-(IC1-SENSOR_VP-Pad4)") (class "Default")
      (node (ref "IC1") (pin "4") (pinfunction "SENSOR_VP_4") (pintype "bidirectional"))
    )
    (net (code "85") (name "unconnected-(J1-Pad3)") (class "Default")
      (node (ref "J1") (pin "3") (pinfunction "3_3") (pintype "passive"))
    )
    (net (code "86") (name "unconnected-(J2-Pad2)") (class "Default")
      (node (ref "J2") (pin "2") (pinfunction "2_2") (pintype "bidirectional"))
    )
    (net (code "87") (name "unconnected-(J2-Pad3)") (class "Default")
      (node (ref "J2") (pin "3") (pinfunction "3_3") (pintype "bidirectional"))
    )
    (net (code "88") (name "unconnected-(J2-Pad4)") (class "Default")
      (node (ref "J2") (pin "4") (pinfunction "4_4") (pintype "bidirectional"))
    )
    (net (code "89") (name "unconnected-(S1-O-Pad1)") (class "Default")
      (node (ref "S1") (pin "1") (pinfunction "O_1") (pintype "passive"))
    )
    (net (code "90") (name "unconnected-(U5-BP-Pad4)") (class "Default")
      (node (ref "U5") (pin "4") (pinfunction "BP_4") (pintype "input"))
    )
    (net (code "91") (name "unconnected-(U6-LINEIN-Pad48)") (class "Default")
      (node (ref "U6") (pin "48") (pinfunction "LINEIN_48") (pintype "bidirectional"))
    )
    (net (code "92") (name "unconnected-(U6-MICN-Pad2)") (class "Default")
      (node (ref "U6") (pin "2") (pinfunction "MICN_2") (pintype "bidirectional"))
    )
    (net (code "93") (name "unconnected-(U6-MICP-Pad1)") (class "Default")
      (node (ref "U6") (pin "1") (pinfunction "MICP_1") (pintype "bidirectional"))
    )
    (net (code "94") (name "unconnected-(U6-TX-Pad27)") (class "Default")
      (node (ref "U6") (pin "27") (pinfunction "TX_27") (pintype "bidirectional"))
    )
    (net (code "95") (name "unconnected-(U6-VCO-Pad15)") (class "Default")
      (node (ref "U6") (pin "15") (pinfunction "VCO_15") (pintype "bidirectional"))
    )
  )
)
